# MainBoard.net
KiCad netlist of a schematic drawn in Altium Designer
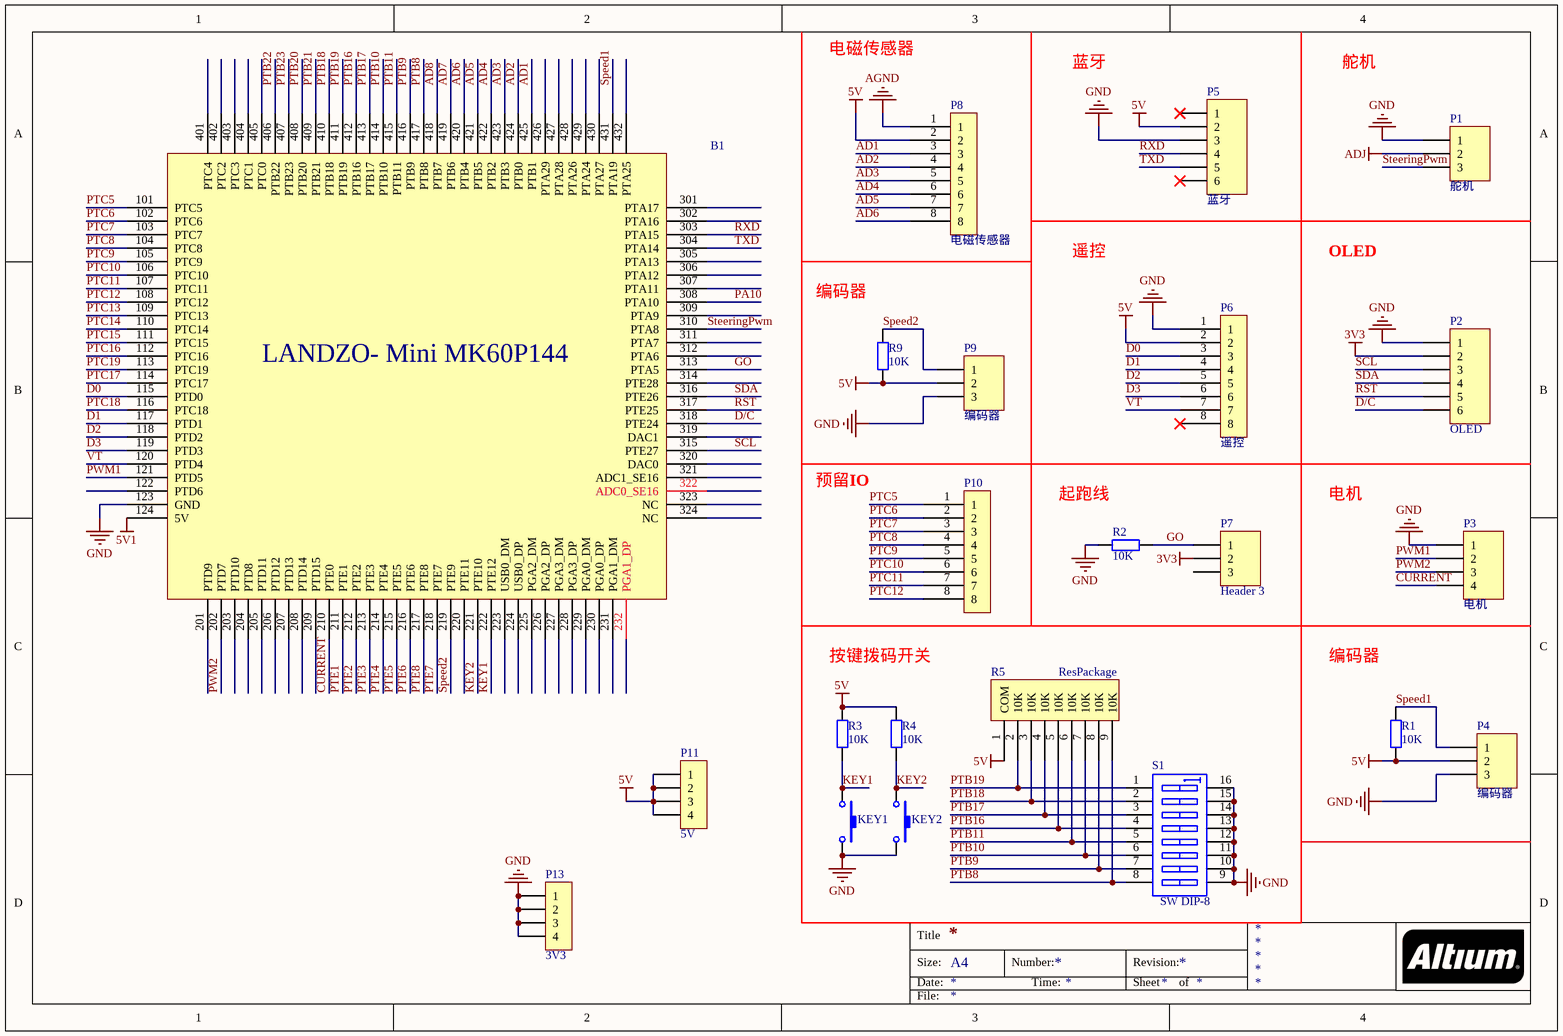
[diagram p0: MainBoard.SchDoc]

(export (version "E")
  (design (tool "Eeschema 10.0.6"))
  (components
    (comp (ref "B1")
      (value "K60P144_system")
      (footprint "锋速MK60P144_system")
      (libsource (lib "蓝宙电子锋速系列主板封装库") (part "锋速MINI K60P144_system"))
    )
    (comp (ref "KEY1")
      (value "SW-4")
      (footprint "SW-4")
      (description "KEY")
      (fields (field (name "PUBLISHER") "Altium Limited"))
      (libsource (lib "My") (part "SW-4"))
    )
    (comp (ref "KEY2")
      (value "SW-4")
      (footprint "SW-4")
      (description "KEY")
      (fields (field (name "PUBLISHER") "Altium Limited"))
      (libsource (lib "My") (part "SW-4"))
    )
    (comp (ref "P1")
      (value "舵机")
      (footprint "XH1X3")
      (description "Header, 3-Pin")
      (fields (field (name "PUBLISHER") "Altium Limited"))
      (libsource (lib "My") (part "Header 3"))
    )
    (comp (ref "P2")
      (value "OLED")
      (footprint "XH2.54_6P2")
      (description "Header, 6-Pin")
      (fields (field (name "PUBLISHER") "Altium Limited"))
      (libsource (lib "My") (part "Header 6"))
    )
    (comp (ref "P3")
      (value "电机")
      (footprint "XH1X4")
      (description "Header, 4-Pin")
      (fields (field (name "PUBLISHER") "Altium Limited"))
      (libsource (lib "My") (part "Header 4"))
    )
    (comp (ref "P4")
      (value "编码器")
      (footprint "XH1X3")
      (description "Header, 3-Pin")
      (fields (field (name "PUBLISHER") "Altium Limited"))
      (libsource (lib "My") (part "Header 3"))
    )
    (comp (ref "P5")
      (value "蓝牙")
      (footprint "XH2.54_6P2")
      (description "Header, 6-Pin")
      (fields (field (name "PUBLISHER") "Altium Limited"))
      (libsource (lib "My") (part "Header 6"))
    )
    (comp (ref "P6")
      (value "遥控")
      (footprint "XH2.54_8P2")
      (description "Header, 4-Pin, Dual row")
      (fields (field (name "PUBLISHER") "Altium Limited"))
      (libsource (lib "蓝宙电子锋速系列主板封装库") (part "Header 8X1A"))
    )
    (comp (ref "P7")
      (value "Header 3")
      (footprint "XH1X3")
      (description "Header, 3-Pin")
      (fields (field (name "PUBLISHER") "Altium Limited"))
      (libsource (lib "My") (part "Header 3"))
    )
    (comp (ref "P8")
      (value "电磁传感器")
      (footprint "XH2.54_8P")
      (description "Header, 4-Pin, Dual row")
      (fields (field (name "PUBLISHER") "Altium Limited"))
      (libsource (lib "蓝宙电子锋速系列主板封装库") (part "Header 8X1A"))
    )
    (comp (ref "P9")
      (value "编码器")
      (footprint "XH1X3")
      (description "Header, 3-Pin")
      (fields (field (name "PUBLISHER") "Altium Limited"))
      (libsource (lib "My") (part "Header 3"))
    )
    (comp (ref "P10")
      (value "~")
      (footprint "XH2.54_8P2")
      (description "Header, 4-Pin, Dual row")
      (fields (field (name "PUBLISHER") "Altium Limited"))
      (libsource (lib "蓝宙电子锋速系列主板封装库") (part "Header 8X1A"))
    )
    (comp (ref "P11")
      (value "5V")
      (footprint "XH2.54_4P2")
      (description "Header, 4-Pin, Dual row")
      (fields (field (name "PUBLISHER") "Altium Limited"))
      (libsource (lib "蓝宙电子锋速系列主板封装库") (part "Header 4X1A"))
    )
    (comp (ref "P13")
      (value "3V3")
      (footprint "XH2.54_4P2")
      (description "Header, 4-Pin, Dual row")
      (fields (field (name "PUBLISHER") "Altium Limited"))
      (libsource (lib "蓝宙电子锋速系列主板封装库") (part "Header 4X1A"))
    )
    (comp (ref "R1")
      (value "10K")
      (footprint "ty0805ss")
      (description "Resistor贴片封装")
      (fields (field (name "Comment") "Res2") (field (name "PUBLISHER") "Altium Limited"))
      (libsource (lib "My") (part "Res2"))
    )
    (comp (ref "R2")
      (value "10K")
      (footprint "ty0805ss")
      (description "Resistor贴片封装")
      (fields (field (name "Comment") "Res2") (field (name "PUBLISHER") "Altium Limited"))
      (libsource (lib "") (part "Res2_1"))
    )
    (comp (ref "R3")
      (value "10K")
      (footprint "ty0805ss")
      (description "Resistor贴片封装")
      (fields (field (name "Comment") "Res2") (field (name "PUBLISHER") "Altium Limited"))
      (libsource (lib "My") (part "Res2"))
    )
    (comp (ref "R4")
      (value "10K")
      (footprint "ty0805ss")
      (description "Resistor贴片封装")
      (fields (field (name "Comment") "Res2") (field (name "PUBLISHER") "Altium Limited"))
      (libsource (lib "My") (part "Res2"))
    )
    (comp (ref "R5") (value "ResPackage") (footprint "HDR1X9") (libsource (lib "My") (part "ResPackage")))
    (comp (ref "R9")
      (value "10K")
      (footprint "ty0805ss")
      (description "Resistor贴片封装")
      (fields (field (name "Comment") "Res2") (field (name "PUBLISHER") "Altium Limited"))
      (libsource (lib "My") (part "Res2"))
    )
    (comp (ref "S1")
      (value "SW DIP-8")
      (footprint "DIP-16")
      (description "DIP Switch, 8 Position, SPST")
      (fields (field (name "PUBLISHER") "Altium Limited"))
      (libsource (lib "Miscellaneous Devices") (part "SW DIP-8"))
    )
  )
  (nets
    (net (code "1") (name "/AD1") (class "Default")
      (node (ref "B1") (pin "425") (pinfunction "PTB1_425") (pintype "passive"))
      (node (ref "P8") (pin "3") (pinfunction "3_3") (pintype "passive"))
    )
    (net (code "2") (name "/AD2") (class "Default")
      (node (ref "B1") (pin "424") (pinfunction "PTB0_424") (pintype "passive"))
      (node (ref "P8") (pin "4") (pinfunction "4_4") (pintype "passive"))
    )
    (net (code "3") (name "/AD3") (class "Default")
      (node (ref "B1") (pin "423") (pinfunction "PTB3_423") (pintype "passive"))
      (node (ref "P8") (pin "5") (pinfunction "5_5") (pintype "passive"))
    )
    (net (code "4") (name "/AD4") (class "Default")
      (node (ref "B1") (pin "422") (pinfunction "PTB2_422") (pintype "passive"))
      (node (ref "P8") (pin "6") (pinfunction "6_6") (pintype "passive"))
    )
    (net (code "5") (name "/AD5") (class "Default")
      (node (ref "B1") (pin "421") (pinfunction "PTB5_421") (pintype "passive"))
      (node (ref "P8") (pin "7") (pinfunction "7_7") (pintype "passive"))
    )
    (net (code "6") (name "/AD6") (class "Default")
      (node (ref "B1") (pin "420") (pinfunction "PTB4_420") (pintype "passive"))
      (node (ref "P8") (pin "8") (pinfunction "8_8") (pintype "passive"))
    )
    (net (code "7") (name "/AD7") (class "Default")
      (node (ref "B1") (pin "419") (pinfunction "PTB6_419") (pintype "passive"))
    )
    (net (code "8") (name "/AD8") (class "Default")
      (node (ref "B1") (pin "418") (pinfunction "PTB7_418") (pintype "passive"))
    )
    (net (code "9") (name "/CURRENT") (class "Default")
      (node (ref "B1") (pin "210") (pinfunction "PTE0_210") (pintype "passive"))
      (node (ref "P3") (pin "4") (pinfunction "4_4") (pintype "passive"))
    )
    (net (code "10") (name "/D0") (class "Default")
      (node (ref "B1") (pin "115") (pinfunction "PTD0_115") (pintype "passive"))
      (node (ref "P6") (pin "3") (pinfunction "3_3") (pintype "passive"))
    )
    (net (code "11") (name "/D1") (class "Default")
      (node (ref "B1") (pin "117") (pinfunction "PTD1_117") (pintype "passive"))
      (node (ref "P6") (pin "4") (pinfunction "4_4") (pintype "passive"))
    )
    (net (code "12") (name "/D2") (class "Default")
      (node (ref "B1") (pin "118") (pinfunction "PTD2_118") (pintype "passive"))
      (node (ref "P6") (pin "5") (pinfunction "5_5") (pintype "passive"))
    )
    (net (code "13") (name "/D3") (class "Default")
      (node (ref "B1") (pin "119") (pinfunction "PTD3_119") (pintype "passive"))
      (node (ref "P6") (pin "6") (pinfunction "6_6") (pintype "passive"))
    )
    (net (code "14") (name "/D{slash}C") (class "Default")
      (node (ref "B1") (pin "318") (pinfunction "PTE24_318") (pintype "passive"))
      (node (ref "P2") (pin "6") (pinfunction "6_6") (pintype "passive"))
    )
    (net (code "15") (name "/GO") (class "Default")
      (node (ref "B1") (pin "313") (pinfunction "PTA5_313") (pintype "passive"))
      (node (ref "P7") (pin "1") (pinfunction "1_1") (pintype "passive"))
      (node (ref "R2") (pin "1") (pinfunction "1_1") (pintype "passive"))
    )
    (net (code "16") (name "/KEY1") (class "Default")
      (node (ref "B1") (pin "222") (pinfunction "PTE12_222") (pintype "passive"))
      (node (ref "KEY1") (pin "1") (pinfunction "1_1") (pintype "passive"))
      (node (ref "R3") (pin "1") (pinfunction "1_1") (pintype "passive"))
    )
    (net (code "17") (name "/KEY2") (class "Default")
      (node (ref "B1") (pin "221") (pinfunction "PTE10_221") (pintype "passive"))
      (node (ref "KEY2") (pin "1") (pinfunction "1_1") (pintype "passive"))
      (node (ref "R4") (pin "1") (pinfunction "1_1") (pintype "passive"))
    )
    (net (code "18") (name "/PA10") (class "Default")
      (node (ref "B1") (pin "308") (pinfunction "PTA10_308") (pintype "passive"))
    )
    (net (code "19") (name "/PTB8") (class "Default")
      (node (ref "B1") (pin "417") (pinfunction "PTB8_417") (pintype "passive"))
      (node (ref "R5") (pin "9") (pinfunction "10K_9") (pintype "passive"))
      (node (ref "S1") (pin "8") (pinfunction "A8_8") (pintype "passive"))
    )
    (net (code "20") (name "/PTB9") (class "Default")
      (node (ref "B1") (pin "416") (pinfunction "PTB9_416") (pintype "passive"))
      (node (ref "R5") (pin "8") (pinfunction "10K_8") (pintype "passive"))
      (node (ref "S1") (pin "7") (pinfunction "A7_7") (pintype "passive"))
    )
    (net (code "21") (name "/PTB10") (class "Default")
      (node (ref "B1") (pin "414") (pinfunction "PTB10_414") (pintype "passive"))
      (node (ref "R5") (pin "7") (pinfunction "10K_7") (pintype "passive"))
      (node (ref "S1") (pin "6") (pinfunction "A6_6") (pintype "passive"))
    )
    (net (code "22") (name "/PTB11") (class "Default")
      (node (ref "B1") (pin "415") (pinfunction "PTB11_415") (pintype "passive"))
      (node (ref "R5") (pin "6") (pinfunction "10K_6") (pintype "passive"))
      (node (ref "S1") (pin "5") (pinfunction "A5_5") (pintype "passive"))
    )
    (net (code "23") (name "/PTB16") (class "Default")
      (node (ref "B1") (pin "412") (pinfunction "PTB16_412") (pintype "passive"))
      (node (ref "R5") (pin "5") (pinfunction "10K_5") (pintype "passive"))
      (node (ref "S1") (pin "4") (pinfunction "A4_4") (pintype "passive"))
    )
    (net (code "24") (name "/PTB17") (class "Default")
      (node (ref "B1") (pin "413") (pinfunction "PTB17_413") (pintype "passive"))
      (node (ref "R5") (pin "4") (pinfunction "10K_4") (pintype "passive"))
      (node (ref "S1") (pin "3") (pinfunction "A3_3") (pintype "passive"))
    )
    (net (code "25") (name "/PTB18") (class "Default")
      (node (ref "B1") (pin "410") (pinfunction "PTB18_410") (pintype "passive"))
      (node (ref "R5") (pin "3") (pinfunction "10K_3") (pintype "passive"))
      (node (ref "S1") (pin "2") (pinfunction "A2_2") (pintype "passive"))
    )
    (net (code "26") (name "/PTB19") (class "Default")
      (node (ref "B1") (pin "411") (pinfunction "PTB19_411") (pintype "passive"))
      (node (ref "R5") (pin "2") (pinfunction "10K_2") (pintype "passive"))
      (node (ref "S1") (pin "1") (pinfunction "A1_1") (pintype "passive"))
    )
    (net (code "27") (name "/PTB20") (class "Default")
      (node (ref "B1") (pin "408") (pinfunction "PTB20_408") (pintype "passive"))
    )
    (net (code "28") (name "/PTB21") (class "Default")
      (node (ref "B1") (pin "409") (pinfunction "PTB21_409") (pintype "passive"))
    )
    (net (code "29") (name "/PTB22") (class "Default")
      (node (ref "B1") (pin "406") (pinfunction "PTB22_406") (pintype "passive"))
    )
    (net (code "30") (name "/PTB23") (class "Default")
      (node (ref "B1") (pin "407") (pinfunction "PTB23_407") (pintype "passive"))
    )
    (net (code "31") (name "/PTC5") (class "Default")
      (node (ref "B1") (pin "101") (pinfunction "PTC5_101") (pintype "passive"))
      (node (ref "P10") (pin "1") (pinfunction "1_1") (pintype "passive"))
    )
    (net (code "32") (name "/PTC6") (class "Default")
      (node (ref "B1") (pin "102") (pinfunction "PTC6_102") (pintype "passive"))
      (node (ref "P10") (pin "2") (pinfunction "2_2") (pintype "passive"))
    )
    (net (code "33") (name "/PTC7") (class "Default")
      (node (ref "B1") (pin "103") (pinfunction "PTC7_103") (pintype "passive"))
      (node (ref "P10") (pin "3") (pinfunction "3_3") (pintype "passive"))
    )
    (net (code "34") (name "/PTC8") (class "Default")
      (node (ref "B1") (pin "104") (pinfunction "PTC8_104") (pintype "passive"))
      (node (ref "P10") (pin "4") (pinfunction "4_4") (pintype "passive"))
    )
    (net (code "35") (name "/PTC9") (class "Default")
      (node (ref "B1") (pin "105") (pinfunction "PTC9_105") (pintype "passive"))
      (node (ref "P10") (pin "5") (pinfunction "5_5") (pintype "passive"))
    )
    (net (code "36") (name "/PTC10") (class "Default")
      (node (ref "B1") (pin "106") (pinfunction "PTC10_106") (pintype "passive"))
      (node (ref "P10") (pin "6") (pinfunction "6_6") (pintype "passive"))
    )
    (net (code "37") (name "/PTC11") (class "Default")
      (node (ref "B1") (pin "107") (pinfunction "PTC11_107") (pintype "passive"))
      (node (ref "P10") (pin "7") (pinfunction "7_7") (pintype "passive"))
    )
    (net (code "38") (name "/PTC12") (class "Default")
      (node (ref "B1") (pin "108") (pinfunction "PTC12_108") (pintype "passive"))
      (node (ref "P10") (pin "8") (pinfunction "8_8") (pintype "passive"))
    )
    (net (code "39") (name "/PTC13") (class "Default")
      (node (ref "B1") (pin "109") (pinfunction "PTC13_109") (pintype "passive"))
    )
    (net (code "40") (name "/PTC14") (class "Default")
      (node (ref "B1") (pin "110") (pinfunction "PTC14_110") (pintype "passive"))
    )
    (net (code "41") (name "/PTC15") (class "Default")
      (node (ref "B1") (pin "111") (pinfunction "PTC15_111") (pintype "passive"))
    )
    (net (code "42") (name "/PTC16") (class "Default")
      (node (ref "B1") (pin "112") (pinfunction "PTC16_112") (pintype "passive"))
    )
    (net (code "43") (name "/PTC17") (class "Default")
      (node (ref "B1") (pin "114") (pinfunction "PTC17_114") (pintype "passive"))
    )
    (net (code "44") (name "/PTC18") (class "Default")
      (node (ref "B1") (pin "116") (pinfunction "PTC18_116") (pintype "passive"))
    )
    (net (code "45") (name "/PTC19") (class "Default")
      (node (ref "B1") (pin "113") (pinfunction "PTC19_113") (pintype "passive"))
    )
    (net (code "46") (name "/PTE1") (class "Default")
      (node (ref "B1") (pin "211") (pinfunction "PTE1_211") (pintype "passive"))
    )
    (net (code "47") (name "/PTE2") (class "Default")
      (node (ref "B1") (pin "212") (pinfunction "PTE2_212") (pintype "passive"))
    )
    (net (code "48") (name "/PTE3") (class "Default")
      (node (ref "B1") (pin "213") (pinfunction "PTE3_213") (pintype "passive"))
    )
    (net (code "49") (name "/PTE4") (class "Default")
      (node (ref "B1") (pin "214") (pinfunction "PTE4_214") (pintype "passive"))
    )
    (net (code "50") (name "/PTE5") (class "Default")
      (node (ref "B1") (pin "215") (pinfunction "PTE5_215") (pintype "passive"))
    )
    (net (code "51") (name "/PTE6") (class "Default")
      (node (ref "B1") (pin "216") (pinfunction "PTE6_216") (pintype "passive"))
    )
    (net (code "52") (name "/PTE7") (class "Default")
      (node (ref "B1") (pin "218") (pinfunction "PTE7_218") (pintype "passive"))
    )
    (net (code "53") (name "/PTE8") (class "Default")
      (node (ref "B1") (pin "217") (pinfunction "PTE8_217") (pintype "passive"))
    )
    (net (code "54") (name "/PWM1") (class "Default")
      (node (ref "B1") (pin "121") (pinfunction "PTD5_121") (pintype "passive"))
      (node (ref "P3") (pin "2") (pinfunction "2_2") (pintype "passive"))
    )
    (net (code "55") (name "/PWM2") (class "Default")
      (node (ref "B1") (pin "202") (pinfunction "PTD7_202") (pintype "passive"))
      (node (ref "P3") (pin "3") (pinfunction "3_3") (pintype "passive"))
    )
    (net (code "56") (name "/RST") (class "Default")
      (node (ref "B1") (pin "317") (pinfunction "PTE25_317") (pintype "passive"))
      (node (ref "P2") (pin "5") (pinfunction "5_5") (pintype "passive"))
    )
    (net (code "57") (name "/RXD") (class "Default")
      (node (ref "B1") (pin "303") (pinfunction "PTA15_303") (pintype "passive"))
      (node (ref "P5") (pin "4") (pinfunction "4_4") (pintype "passive"))
    )
    (net (code "58") (name "/SCL") (class "Default")
      (node (ref "B1") (pin "315") (pinfunction "PTE27_315") (pintype "passive"))
      (node (ref "P2") (pin "3") (pinfunction "3_3") (pintype "passive"))
    )
    (net (code "59") (name "/SDA") (class "Default")
      (node (ref "B1") (pin "316") (pinfunction "PTE26_316") (pintype "passive"))
      (node (ref "P2") (pin "4") (pinfunction "4_4") (pintype "passive"))
    )
    (net (code "60") (name "/Speed1") (class "Default")
      (node (ref "B1") (pin "431") (pinfunction "PTA19_431") (pintype "passive"))
      (node (ref "P4") (pin "1") (pinfunction "1_1") (pintype "passive"))
      (node (ref "R1") (pin "2") (pinfunction "2_2") (pintype "passive"))
    )
    (net (code "61") (name "/Speed2") (class "Default")
      (node (ref "B1") (pin "219") (pinfunction "PTE9_219") (pintype "passive"))
      (node (ref "P9") (pin "1") (pinfunction "1_1") (pintype "passive"))
      (node (ref "R9") (pin "2") (pinfunction "2_2") (pintype "passive"))
    )
    (net (code "62") (name "/SteeringPwm") (class "Default")
      (node (ref "B1") (pin "310") (pinfunction "PTA8_310") (pintype "passive"))
      (node (ref "P1") (pin "3") (pinfunction "3_3") (pintype "passive"))
    )
    (net (code "63") (name "/TXD") (class "Default")
      (node (ref "B1") (pin "304") (pinfunction "PTA14_304") (pintype "passive"))
      (node (ref "P5") (pin "5") (pinfunction "5_5") (pintype "passive"))
    )
    (net (code "64") (name "/VT") (class "Default")
      (node (ref "B1") (pin "120") (pinfunction "PTD4_120") (pintype "passive"))
      (node (ref "P6") (pin "7") (pinfunction "7_7") (pintype "passive"))
    )
    (net (code "65") (name "3V3") (class "Default")
      (node (ref "P2") (pin "2") (pinfunction "2_2") (pintype "passive"))
      (node (ref "P7") (pin "2") (pinfunction "2_2") (pintype "passive"))
    )
    (net (code "66") (name "5V") (class "Default")
      (node (ref "P11") (pin "1") (pinfunction "1_1") (pintype "passive"))
      (node (ref "P11") (pin "2") (pinfunction "2_2") (pintype "passive"))
      (node (ref "P11") (pin "3") (pinfunction "3_3") (pintype "passive"))
      (node (ref "P11") (pin "4") (pinfunction "4_4") (pintype "passive"))
      (node (ref "P4") (pin "2") (pinfunction "2_2") (pintype "passive"))
      (node (ref "P5") (pin "2") (pinfunction "2_2") (pintype "passive"))
      (node (ref "P6") (pin "2") (pinfunction "2_2") (pintype "passive"))
      (node (ref "P8") (pin "2") (pinfunction "2_2") (pintype "passive"))
      (node (ref "P9") (pin "2") (pinfunction "2_2") (pintype "passive"))
      (node (ref "R1") (pin "1") (pinfunction "1_1") (pintype "passive"))
      (node (ref "R3") (pin "2") (pinfunction "2_2") (pintype "passive"))
      (node (ref "R4") (pin "2") (pinfunction "2_2") (pintype "passive"))
      (node (ref "R5") (pin "1") (pinfunction "COM_1") (pintype "passive"))
      (node (ref "R9") (pin "1") (pinfunction "1_1") (pintype "passive"))
    )
    (net (code "67") (name "5V1") (class "Default")
      (node (ref "B1") (pin "124") (pinfunction "5V_124") (pintype "passive"))
    )
    (net (code "68") (name "ADJ") (class "Default")
      (node (ref "P1") (pin "2") (pinfunction "2_2") (pintype "passive"))
    )
    (net (code "69") (name "AGND") (class "Default")
      (node (ref "P8") (pin "1") (pinfunction "1_1") (pintype "passive"))
    )
    (net (code "70") (name "GND") (class "Default")
      (node (ref "B1") (pin "123") (pinfunction "GND_123") (pintype "passive"))
      (node (ref "KEY1") (pin "2") (pinfunction "2_2") (pintype "passive"))
      (node (ref "KEY2") (pin "2") (pinfunction "2_2") (pintype "passive"))
      (node (ref "P1") (pin "1") (pinfunction "1_1") (pintype "passive"))
      (node (ref "P13") (pin "1") (pinfunction "1_1") (pintype "passive"))
      (node (ref "P13") (pin "2") (pinfunction "2_2") (pintype "passive"))
      (node (ref "P13") (pin "3") (pinfunction "3_3") (pintype "passive"))
      (node (ref "P13") (pin "4") (pinfunction "4_4") (pintype "passive"))
      (node (ref "P2") (pin "1") (pinfunction "1_1") (pintype "passive"))
      (node (ref "P3") (pin "1") (pinfunction "1_1") (pintype "passive"))
      (node (ref "P4") (pin "3") (pinfunction "3_3") (pintype "passive"))
      (node (ref "P5") (pin "3") (pinfunction "3_3") (pintype "passive"))
      (node (ref "P6") (pin "1") (pinfunction "1_1") (pintype "passive"))
      (node (ref "P9") (pin "3") (pinfunction "3_3") (pintype "passive"))
      (node (ref "R2") (pin "2") (pinfunction "2_2") (pintype "passive"))
      (node (ref "S1") (pin "10") (pinfunction "B7_10") (pintype "passive"))
      (node (ref "S1") (pin "11") (pinfunction "B6_11") (pintype "passive"))
      (node (ref "S1") (pin "12") (pinfunction "B5_12") (pintype "passive"))
      (node (ref "S1") (pin "13") (pinfunction "B4_13") (pintype "passive"))
      (node (ref "S1") (pin "14") (pinfunction "B3_14") (pintype "passive"))
      (node (ref "S1") (pin "15") (pinfunction "B2_15") (pintype "passive"))
      (node (ref "S1") (pin "16") (pinfunction "B1_16") (pintype "passive"))
      (node (ref "S1") (pin "9") (pinfunction "B8_9") (pintype "passive"))
    )
    (net (code "71") (name "unconnected-(B1-ADC0_SE16-Pad322)") (class "Default")
      (node (ref "B1") (pin "322") (pinfunction "ADC0_SE16_322") (pintype "passive"))
    )
    (net (code "72") (name "unconnected-(B1-ADC1_SE16-Pad321)") (class "Default")
      (node (ref "B1") (pin "321") (pinfunction "ADC1_SE16_321") (pintype "passive"))
    )
    (net (code "73") (name "unconnected-(B1-DAC0-Pad320)") (class "Default")
      (node (ref "B1") (pin "320") (pinfunction "DAC0_320") (pintype "passive"))
    )
    (net (code "74") (name "unconnected-(B1-DAC1-Pad319)") (class "Default")
      (node (ref "B1") (pin "319") (pinfunction "DAC1_319") (pintype "passive"))
    )
    (net (code "75") (name "unconnected-(B1-NC-Pad323)") (class "Default")
      (node (ref "B1") (pin "323") (pinfunction "NC_323") (pintype "passive"))
    )
    (net (code "76") (name "unconnected-(B1-NC-Pad324)") (class "Default")
      (node (ref "B1") (pin "324") (pinfunction "NC_324") (pintype "passive"))
    )
    (net (code "77") (name "unconnected-(B1-PGA0_DM-Pad229)") (class "Default")
      (node (ref "B1") (pin "229") (pinfunction "PGA0_DM_229") (pintype "passive"))
    )
    (net (code "78") (name "unconnected-(B1-PGA0_DP-Pad230)") (class "Default")
      (node (ref "B1") (pin "230") (pinfunction "PGA0_DP_230") (pintype "passive"))
    )
    (net (code "79") (name "unconnected-(B1-PGA1_DM-Pad231)") (class "Default")
      (node (ref "B1") (pin "231") (pinfunction "PGA1_DM_231") (pintype "passive"))
    )
    (net (code "80") (name "unconnected-(B1-PGA1_DP-Pad232)") (class "Default")
      (node (ref "B1") (pin "232") (pinfunction "PGA1_DP_232") (pintype "passive"))
    )
    (net (code "81") (name "unconnected-(B1-PGA2_DM-Pad225)") (class "Default")
      (node (ref "B1") (pin "225") (pinfunction "PGA2_DM_225") (pintype "passive"))
    )
    (net (code "82") (name "unconnected-(B1-PGA2_DP-Pad226)") (class "Default")
      (node (ref "B1") (pin "226") (pinfunction "PGA2_DP_226") (pintype "passive"))
    )
    (net (code "83") (name "unconnected-(B1-PGA3_DM-Pad227)") (class "Default")
      (node (ref "B1") (pin "227") (pinfunction "PGA3_DM_227") (pintype "passive"))
    )
    (net (code "84") (name "unconnected-(B1-PGA3_DP-Pad228)") (class "Default")
      (node (ref "B1") (pin "228") (pinfunction "PGA3_DP_228") (pintype "passive"))
    )
    (net (code "85") (name "unconnected-(B1-PTA6-Pad312)") (class "Default")
      (node (ref "B1") (pin "312") (pinfunction "PTA6_312") (pintype "passive"))
    )
    (net (code "86") (name "unconnected-(B1-PTA7-Pad311)") (class "Default")
      (node (ref "B1") (pin "311") (pinfunction "PTA7_311") (pintype "passive"))
    )
    (net (code "87") (name "unconnected-(B1-PTA9-Pad309)") (class "Default")
      (node (ref "B1") (pin "309") (pinfunction "PTA9_309") (pintype "passive"))
    )
    (net (code "88") (name "unconnected-(B1-PTA11-Pad307)") (class "Default")
      (node (ref "B1") (pin "307") (pinfunction "PTA11_307") (pintype "passive"))
    )
    (net (code "89") (name "unconnected-(B1-PTA12-Pad306)") (class "Default")
      (node (ref "B1") (pin "306") (pinfunction "PTA12_306") (pintype "passive"))
    )
    (net (code "90") (name "unconnected-(B1-PTA13-Pad305)") (class "Default")
      (node (ref "B1") (pin "305") (pinfunction "PTA13_305") (pintype "passive"))
    )
    (net (code "91") (name "unconnected-(B1-PTA16-Pad302)") (class "Default")
      (node (ref "B1") (pin "302") (pinfunction "PTA16_302") (pintype "passive"))
    )
    (net (code "92") (name "unconnected-(B1-PTA17-Pad301)") (class "Default")
      (node (ref "B1") (pin "301") (pinfunction "PTA17_301") (pintype "passive"))
    )
    (net (code "93") (name "unconnected-(B1-PTA24-Pad429)") (class "Default")
      (node (ref "B1") (pin "429") (pinfunction "PTA24_429") (pintype "passive"))
    )
    (net (code "94") (name "unconnected-(B1-PTA25-Pad432)") (class "Default")
      (node (ref "B1") (pin "432") (pinfunction "PTA25_432") (pintype "passive"))
    )
    (net (code "95") (name "unconnected-(B1-PTA26-Pad428)") (class "Default")
      (node (ref "B1") (pin "428") (pinfunction "PTA26_428") (pintype "passive"))
    )
    (net (code "96") (name "unconnected-(B1-PTA27-Pad430)") (class "Default")
      (node (ref "B1") (pin "430") (pinfunction "PTA27_430") (pintype "passive"))
    )
    (net (code "97") (name "unconnected-(B1-PTA28-Pad427)") (class "Default")
      (node (ref "B1") (pin "427") (pinfunction "PTA28_427") (pintype "passive"))
    )
    (net (code "98") (name "unconnected-(B1-PTA29-Pad426)") (class "Default")
      (node (ref "B1") (pin "426") (pinfunction "PTA29_426") (pintype "passive"))
    )
    (net (code "99") (name "unconnected-(B1-PTC0-Pad405)") (class "Default")
      (node (ref "B1") (pin "405") (pinfunction "PTC0_405") (pintype "passive"))
    )
    (net (code "100") (name "unconnected-(B1-PTC1-Pad404)") (class "Default")
      (node (ref "B1") (pin "404") (pinfunction "PTC1_404") (pintype "passive"))
    )
    (net (code "101") (name "unconnected-(B1-PTC2-Pad402)") (class "Default")
      (node (ref "B1") (pin "402") (pinfunction "PTC2_402") (pintype "passive"))
    )
    (net (code "102") (name "unconnected-(B1-PTC3-Pad403)") (class "Default")
      (node (ref "B1") (pin "403") (pinfunction "PTC3_403") (pintype "passive"))
    )
    (net (code "103") (name "unconnected-(B1-PTC4-Pad401)") (class "Default")
      (node (ref "B1") (pin "401") (pinfunction "PTC4_401") (pintype "passive"))
    )
    (net (code "104") (name "unconnected-(B1-PTD6-Pad122)") (class "Default")
      (node (ref "B1") (pin "122") (pinfunction "PTD6_122") (pintype "passive"))
    )
    (net (code "105") (name "unconnected-(B1-PTD8-Pad204)") (class "Default")
      (node (ref "B1") (pin "204") (pinfunction "PTD8_204") (pintype "passive"))
    )
    (net (code "106") (name "unconnected-(B1-PTD9-Pad201)") (class "Default")
      (node (ref "B1") (pin "201") (pinfunction "PTD9_201") (pintype "passive"))
    )
    (net (code "107") (name "unconnected-(B1-PTD10-Pad203)") (class "Default")
      (node (ref "B1") (pin "203") (pinfunction "PTD10_203") (pintype "passive"))
    )
    (net (code "108") (name "unconnected-(B1-PTD11-Pad205)") (class "Default")
      (node (ref "B1") (pin "205") (pinfunction "PTD11_205") (pintype "passive"))
    )
    (net (code "109") (name "unconnected-(B1-PTD12-Pad206)") (class "Default")
      (node (ref "B1") (pin "206") (pinfunction "PTD12_206") (pintype "passive"))
    )
    (net (code "110") (name "unconnected-(B1-PTD13-Pad207)") (class "Default")
      (node (ref "B1") (pin "207") (pinfunction "PTD13_207") (pintype "passive"))
    )
    (net (code "111") (name "unconnected-(B1-PTD14-Pad208)") (class "Default")
      (node (ref "B1") (pin "208") (pinfunction "PTD14_208") (pintype "passive"))
    )
    (net (code "112") (name "unconnected-(B1-PTD15-Pad209)") (class "Default")
      (node (ref "B1") (pin "209") (pinfunction "PTD15_209") (pintype "passive"))
    )
    (net (code "113") (name "unconnected-(B1-PTE11-Pad220)") (class "Default")
      (node (ref "B1") (pin "220") (pinfunction "PTE11_220") (pintype "passive"))
    )
    (net (code "114") (name "unconnected-(B1-PTE28-Pad314)") (class "Default")
      (node (ref "B1") (pin "314") (pinfunction "PTE28_314") (pintype "passive"))
    )
    (net (code "115") (name "unconnected-(B1-USB0_DM-Pad223)") (class "Default")
      (node (ref "B1") (pin "223") (pinfunction "USB0_DM_223") (pintype "passive"))
    )
    (net (code "116") (name "unconnected-(B1-USB0_DP-Pad224)") (class "Default")
      (node (ref "B1") (pin "224") (pinfunction "USB0_DP_224") (pintype "passive"))
    )
    (net (code "117") (name "unconnected-(P5-Pad1)") (class "Default")
      (node (ref "P5") (pin "1") (pinfunction "1_1") (pintype "passive+no_connect"))
    )
    (net (code "118") (name "unconnected-(P5-Pad6)") (class "Default")
      (node (ref "P5") (pin "6") (pinfunction "6_6") (pintype "passive+no_connect"))
    )
    (net (code "119") (name "unconnected-(P6-Pad8)") (class "Default")
      (node (ref "P6") (pin "8") (pinfunction "8_8") (pintype "passive+no_connect"))
    )
    (net (code "120") (name "unconnected-(P7-Pad3)") (class "Default")
      (node (ref "P7") (pin "3") (pinfunction "3_3") (pintype "passive"))
    )
  )
)
